# DensityAltitude_BME280_7SEG.net
KiCad netlist of a schematic drawn in EAGLE
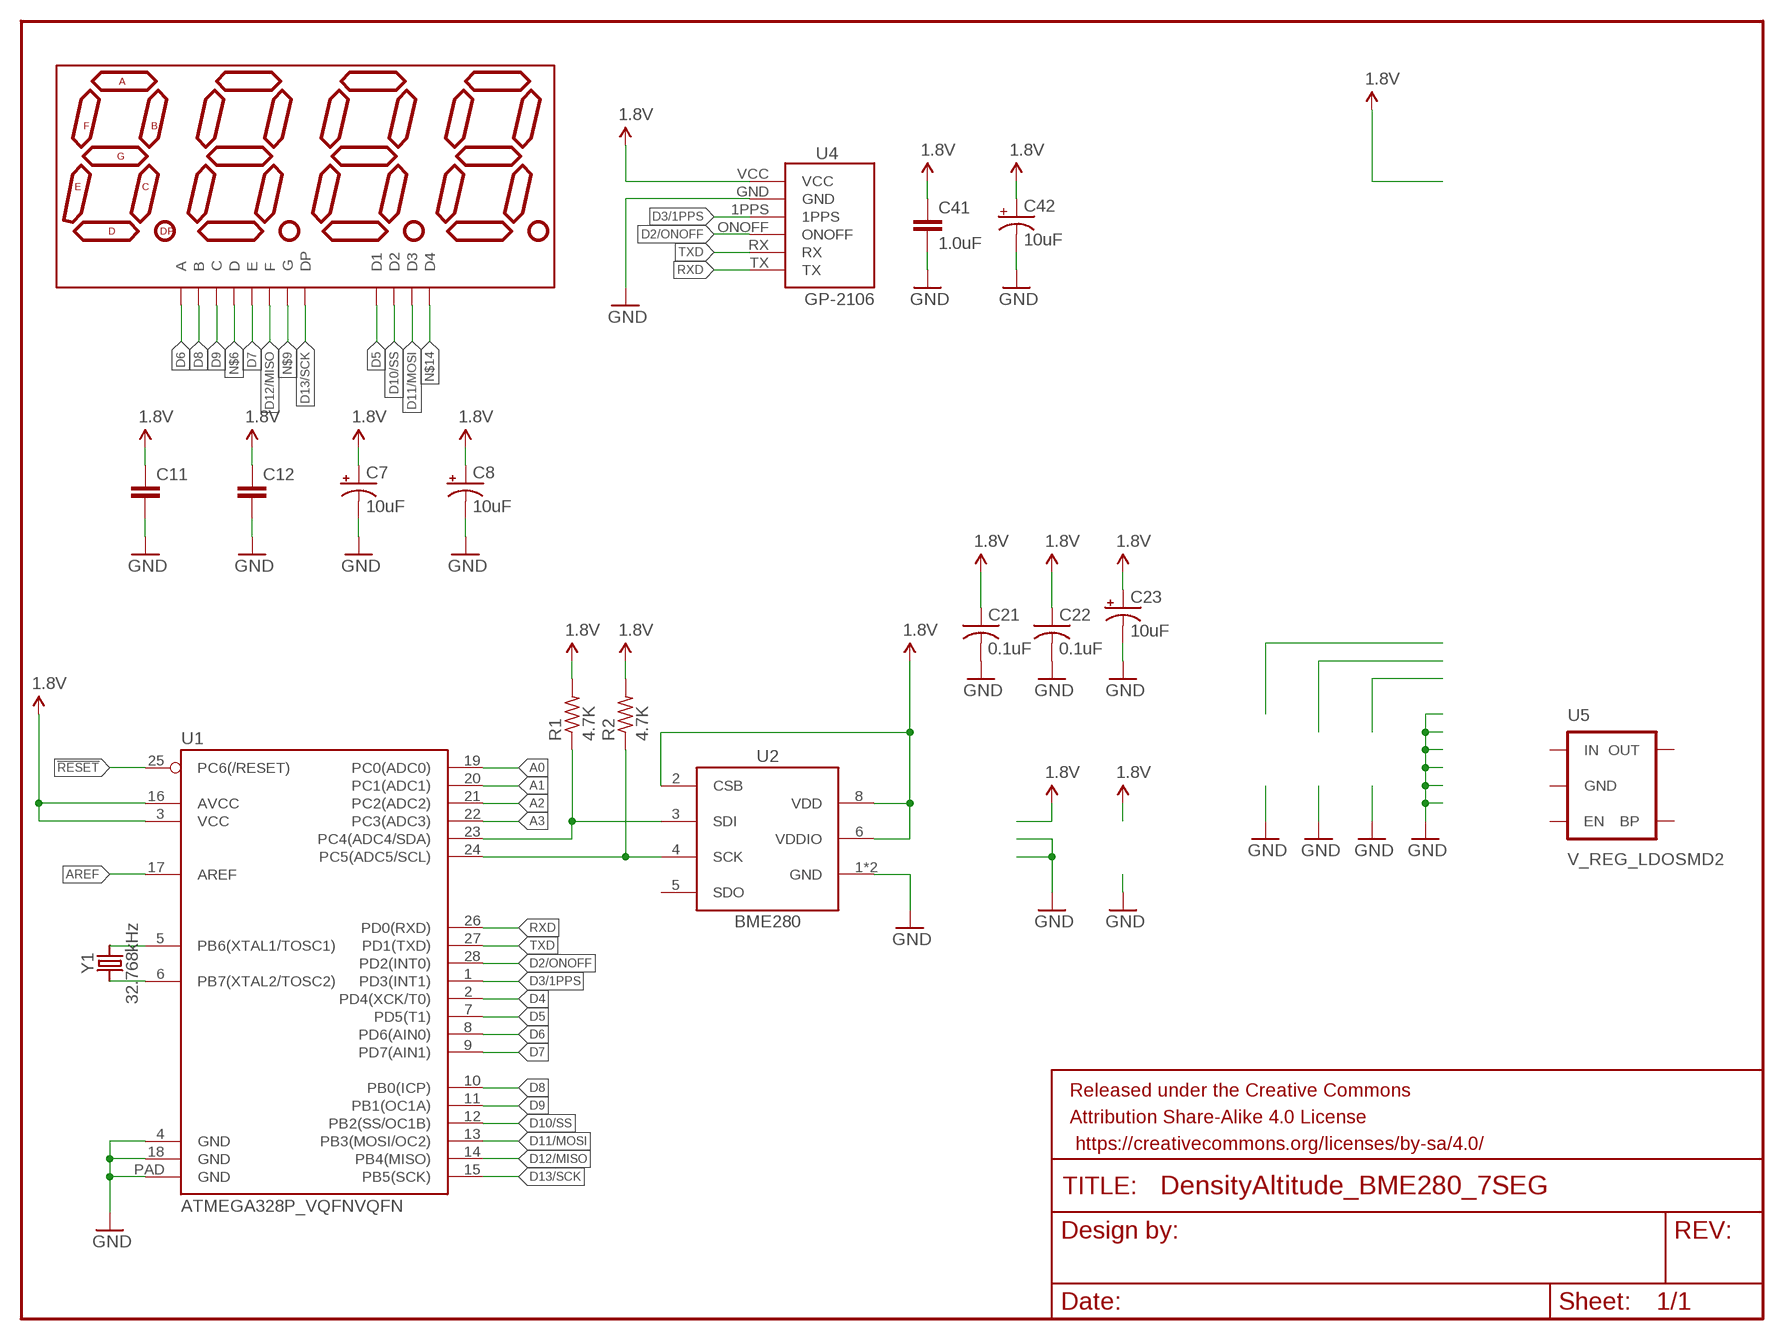
[diagram p0: schematic, sheet 1]

(export (version "E")
  (design (tool "Eeschema 10.0.6"))
  (components
    (comp (ref "C7")
      (value "10uF")
      (footprint "eagle-import:EIA3216")
      (libsource (lib "eagle-import") (part "10UF-16V-10%(TANT)"))
    )
    (comp (ref "C8")
      (value "10uF")
      (footprint "eagle-import:EIA3216")
      (libsource (lib "eagle-import") (part "10UF-16V-10%(TANT)"))
    )
    (comp (ref "C11")
      (value "CAP0402-CAP")
      (footprint "eagle-import:0402-CAP")
      (libsource (lib "eagle-import") (part "CAP0402-CAP"))
    )
    (comp (ref "C12")
      (value "CAP0402-CAP")
      (footprint "eagle-import:0402-CAP")
      (libsource (lib "eagle-import") (part "CAP0402-CAP"))
    )
    (comp (ref "C21")
      (value "0.1uF")
      (footprint "eagle-import:C0201")
      (libsource (lib "eagle-import") (part "C-USC0201"))
    )
    (comp (ref "C22")
      (value "0.1uF")
      (footprint "eagle-import:C0201")
      (libsource (lib "eagle-import") (part "C-USC0201"))
    )
    (comp (ref "C23")
      (value "10uF")
      (footprint "eagle-import:EIA3216")
      (libsource (lib "eagle-import") (part "10UF-16V-10%(TANT)"))
    )
    (comp (ref "C41")
      (value "1.0uF")
      (footprint "eagle-import:0402-CAP")
      (libsource (lib "eagle-import") (part "1.0UF-16V-10%(0402)"))
    )
    (comp (ref "C42")
      (value "10uF")
      (footprint "eagle-import:EIA3216")
      (libsource (lib "eagle-import") (part "10UF-16V-10%(TANT)"))
    )
    (comp (ref "DISP1")
      (value "7-SEGMENT-4DIGIT-COUNTER-HP-BUBBLE")
      (footprint "eagle-import:DIL12")
      (libsource (lib "eagle-import") (part "7-SEGMENT-4DIGIT-COUNTER-HP-BUBBLE"))
    )
    (comp (ref "FRAME1")
      (value "FRAME-LETTER")
      (footprint "eagle-import:CREATIVE_COMMONS")
      (fields (field (name "DESIGNER") "NAME"))
      (libsource (lib "eagle-import") (part "FRAME-LETTER"))
    )
    (comp (ref "R1")
      (value "4.7K")
      (footprint "eagle-import:R0201")
      (libsource (lib "eagle-import") (part "R-US_R0201"))
    )
    (comp (ref "R2")
      (value "4.7K")
      (footprint "eagle-import:R0201")
      (libsource (lib "eagle-import") (part "R-US_R0201"))
    )
    (comp (ref "U1")
      (value "ATMEGA328P_VQFNVQFN")
      (footprint "eagle-import:VQFN-28")
      (libsource (lib "eagle-import") (part "ATMEGA328P_VQFNVQFN"))
    )
    (comp (ref "U2")
      (value "BME280")
      (footprint "eagle-import:BME280")
      (libsource (lib "eagle-import") (part "BME280"))
    )
    (comp (ref "U4")
      (value "GP-2106")
      (footprint "eagle-import:GP-2106")
      (libsource (lib "eagle-import") (part "GP-2106"))
    )
    (comp (ref "U5")
      (value "V_REG_LDOSMD2")
      (footprint "eagle-import:SC70")
      (libsource (lib "eagle-import") (part "V_REG_LDOSMD2"))
    )
    (comp (ref "Y1")
      (value "32.768kHz")
      (footprint "eagle-import:2-SMD")
      (libsource (lib "eagle-import") (part "FX12232.768KHZ"))
    )
  )
  (nets
    (net (code "1") (name "/~{RESET}") (class "Default")
      (node (ref "U1") (pin "25") (pinfunction "PC6(/RESET)_25") (pintype "bidirectional"))
    )
    (net (code "2") (name "1.8V") (class "Default")
      (node (ref "C11") (pin "1") (pinfunction "1_1") (pintype "passive"))
      (node (ref "C12") (pin "1") (pinfunction "1_1") (pintype "passive"))
      (node (ref "C21") (pin "1") (pinfunction "1_1") (pintype "passive"))
      (node (ref "C22") (pin "1") (pinfunction "1_1") (pintype "passive"))
      (node (ref "C23") (pin "A") (pinfunction "+_A") (pintype "passive"))
      (node (ref "C41") (pin "1") (pinfunction "1_1") (pintype "passive"))
      (node (ref "C42") (pin "A") (pinfunction "+_A") (pintype "passive"))
      (node (ref "C7") (pin "A") (pinfunction "+_A") (pintype "passive"))
      (node (ref "C8") (pin "A") (pinfunction "+_A") (pintype "passive"))
      (node (ref "R1") (pin "2") (pinfunction "2_2") (pintype "passive"))
      (node (ref "R2") (pin "2") (pinfunction "2_2") (pintype "passive"))
      (node (ref "U1") (pin "16") (pinfunction "AVCC_16") (pintype "bidirectional"))
      (node (ref "U1") (pin "3") (pinfunction "VCC_3") (pintype "bidirectional"))
      (node (ref "U2") (pin "2") (pinfunction "CSB_2") (pintype "input"))
      (node (ref "U2") (pin "6") (pinfunction "VDDIO_6") (pintype "power_in"))
      (node (ref "U2") (pin "8") (pinfunction "VDD_8") (pintype "power_in"))
      (node (ref "U4") (pin "VCC") (pinfunction "VCC_VCC") (pintype "bidirectional"))
    )
    (net (code "3") (name "A0") (class "Default")
      (node (ref "U1") (pin "19") (pinfunction "PC0(ADC0)_19") (pintype "bidirectional"))
    )
    (net (code "4") (name "A1") (class "Default")
      (node (ref "U1") (pin "20") (pinfunction "PC1(ADC1)_20") (pintype "bidirectional"))
    )
    (net (code "5") (name "A2") (class "Default")
      (node (ref "U1") (pin "21") (pinfunction "PC2(ADC2)_21") (pintype "bidirectional"))
    )
    (net (code "6") (name "A3") (class "Default")
      (node (ref "U1") (pin "22") (pinfunction "PC3(ADC3)_22") (pintype "bidirectional"))
    )
    (net (code "7") (name "AREF") (class "Default")
      (node (ref "U1") (pin "17") (pinfunction "AREF_17") (pintype "bidirectional"))
    )
    (net (code "8") (name "D2{slash}ONOFF") (class "Default")
      (node (ref "U1") (pin "28") (pinfunction "PD2(INT0)_28") (pintype "bidirectional"))
      (node (ref "U4") (pin "ONOFF") (pinfunction "ONOFF_ONOFF") (pintype "bidirectional"))
    )
    (net (code "9") (name "D3{slash}1PPS") (class "Default")
      (node (ref "U1") (pin "1") (pinfunction "PD3(INT1)_1") (pintype "bidirectional"))
      (node (ref "U4") (pin "1PPS") (pinfunction "1PPS_1PPS") (pintype "bidirectional"))
    )
    (net (code "10") (name "D4") (class "Default")
      (node (ref "U1") (pin "2") (pinfunction "PD4(XCK/T0)_2") (pintype "bidirectional"))
    )
    (net (code "11") (name "D5") (class "Default")
      (node (ref "DISP1") (pin "1") (pinfunction "D1_1") (pintype "bidirectional"))
      (node (ref "U1") (pin "7") (pinfunction "PD5(T1)_7") (pintype "bidirectional"))
    )
    (net (code "12") (name "D6") (class "Default")
      (node (ref "DISP1") (pin "12") (pinfunction "A_12") (pintype "bidirectional"))
      (node (ref "U1") (pin "8") (pinfunction "PD6(AIN0)_8") (pintype "bidirectional"))
    )
    (net (code "13") (name "D7") (class "Default")
      (node (ref "DISP1") (pin "2") (pinfunction "E_2") (pintype "bidirectional"))
      (node (ref "U1") (pin "9") (pinfunction "PD7(AIN1)_9") (pintype "bidirectional"))
    )
    (net (code "14") (name "D8") (class "Default")
      (node (ref "DISP1") (pin "11") (pinfunction "B_11") (pintype "bidirectional"))
      (node (ref "U1") (pin "10") (pinfunction "PB0(ICP)_10") (pintype "bidirectional"))
    )
    (net (code "15") (name "D9") (class "Default")
      (node (ref "DISP1") (pin "3") (pinfunction "C_3") (pintype "bidirectional"))
      (node (ref "U1") (pin "11") (pinfunction "PB1(OC1A)_11") (pintype "bidirectional"))
    )
    (net (code "16") (name "D10{slash}SS") (class "Default")
      (node (ref "DISP1") (pin "10") (pinfunction "D2_10") (pintype "bidirectional"))
      (node (ref "U1") (pin "12") (pinfunction "PB2(SS/OC1B)_12") (pintype "bidirectional"))
    )
    (net (code "17") (name "D11{slash}MOSI") (class "Default")
      (node (ref "DISP1") (pin "4") (pinfunction "D3_4") (pintype "bidirectional"))
      (node (ref "U1") (pin "13") (pinfunction "PB3(MOSI/OC2)_13") (pintype "bidirectional"))
    )
    (net (code "18") (name "D12{slash}MISO") (class "Default")
      (node (ref "DISP1") (pin "9") (pinfunction "F_9") (pintype "bidirectional"))
      (node (ref "U1") (pin "14") (pinfunction "PB4(MISO)_14") (pintype "bidirectional"))
    )
    (net (code "19") (name "D13{slash}SCK") (class "Default")
      (node (ref "DISP1") (pin "5") (pinfunction "DP_5") (pintype "bidirectional"))
      (node (ref "U1") (pin "15") (pinfunction "PB5(SCK)_15") (pintype "bidirectional"))
    )
    (net (code "20") (name "GND") (class "Default")
      (node (ref "C11") (pin "2") (pinfunction "2_2") (pintype "passive"))
      (node (ref "C12") (pin "2") (pinfunction "2_2") (pintype "passive"))
      (node (ref "C21") (pin "2") (pinfunction "2_2") (pintype "passive"))
      (node (ref "C22") (pin "2") (pinfunction "2_2") (pintype "passive"))
      (node (ref "C23") (pin "C") (pinfunction "-_C") (pintype "passive"))
      (node (ref "C41") (pin "2") (pinfunction "2_2") (pintype "passive"))
      (node (ref "C42") (pin "C") (pinfunction "-_C") (pintype "passive"))
      (node (ref "C7") (pin "C") (pinfunction "-_C") (pintype "passive"))
      (node (ref "C8") (pin "C") (pinfunction "-_C") (pintype "passive"))
      (node (ref "U1") (pin "18") (pinfunction "GND_18") (pintype "bidirectional"))
      (node (ref "U1") (pin "4") (pinfunction "GND_4") (pintype "bidirectional"))
      (node (ref "U1") (pin "PAD") (pinfunction "GND_PAD") (pintype "bidirectional"))
      (node (ref "U2") (pin "1") (pinfunction "GND_1") (pintype "passive"))
      (node (ref "U2") (pin "7") (pinfunction "GND_7") (pintype "passive"))
      (node (ref "U4") (pin "GND") (pinfunction "GND_GND") (pintype "bidirectional"))
    )
    (net (code "21") (name "N$6") (class "Default")
      (node (ref "DISP1") (pin "8") (pinfunction "D_8") (pintype "bidirectional"))
    )
    (net (code "22") (name "N$9") (class "Default")
      (node (ref "DISP1") (pin "7") (pinfunction "G_7") (pintype "bidirectional"))
    )
    (net (code "23") (name "N$14") (class "Default")
      (node (ref "DISP1") (pin "6") (pinfunction "D4_6") (pintype "bidirectional"))
    )
    (net (code "24") (name "Net-(U1-PB6(XTAL1{slash}TOSC1))") (class "Default")
      (node (ref "U1") (pin "5") (pinfunction "PB6(XTAL1/TOSC1)_5") (pintype "bidirectional"))
      (node (ref "Y1") (pin "2") (pinfunction "2_2") (pintype "passive"))
    )
    (net (code "25") (name "Net-(U1-PB7(XTAL2{slash}TOSC2))") (class "Default")
      (node (ref "U1") (pin "6") (pinfunction "PB7(XTAL2/TOSC2)_6") (pintype "bidirectional"))
      (node (ref "Y1") (pin "1") (pinfunction "1_1") (pintype "passive"))
    )
    (net (code "26") (name "Net-(U1-PC4(ADC4{slash}SDA))") (class "Default")
      (node (ref "R1") (pin "1") (pinfunction "1_1") (pintype "passive"))
      (node (ref "U1") (pin "23") (pinfunction "PC4(ADC4/SDA)_23") (pintype "bidirectional"))
      (node (ref "U2") (pin "3") (pinfunction "SDI_3") (pintype "bidirectional"))
    )
    (net (code "27") (name "Net-(U1-PC5(ADC5{slash}SCL))") (class "Default")
      (node (ref "R2") (pin "1") (pinfunction "1_1") (pintype "passive"))
      (node (ref "U1") (pin "24") (pinfunction "PC5(ADC5/SCL)_24") (pintype "bidirectional"))
      (node (ref "U2") (pin "4") (pinfunction "SCK_4") (pintype "input"))
    )
    (net (code "28") (name "RXD") (class "Default")
      (node (ref "U1") (pin "26") (pinfunction "PD0(RXD)_26") (pintype "bidirectional"))
      (node (ref "U4") (pin "TX") (pinfunction "TX_TX") (pintype "bidirectional"))
    )
    (net (code "29") (name "TXD") (class "Default")
      (node (ref "U1") (pin "27") (pinfunction "PD1(TXD)_27") (pintype "bidirectional"))
      (node (ref "U4") (pin "RX") (pinfunction "RX_RX") (pintype "bidirectional"))
    )
    (net (code "30") (name "unconnected-(U2-SDO-Pad5)") (class "Default")
      (node (ref "U2") (pin "5") (pinfunction "SDO_5") (pintype "bidirectional"))
    )
    (net (code "31") (name "unconnected-(U5-BP-Pad4)") (class "Default")
      (node (ref "U5") (pin "4") (pinfunction "BP_4") (pintype "input"))
    )
    (net (code "32") (name "unconnected-(U5-EN-Pad3)") (class "Default")
      (node (ref "U5") (pin "3") (pinfunction "EN_3") (pintype "input"))
    )
    (net (code "33") (name "unconnected-(U5-GND-Pad2)") (class "Default")
      (node (ref "U5") (pin "2") (pinfunction "GND_2") (pintype "input"))
    )
    (net (code "34") (name "unconnected-(U5-IN-Pad1)") (class "Default")
      (node (ref "U5") (pin "1") (pinfunction "IN_1") (pintype "input"))
    )
    (net (code "35") (name "unconnected-(U5-OUT-Pad5)") (class "Default")
      (node (ref "U5") (pin "5") (pinfunction "OUT_5") (pintype "passive"))
    )
  )
)
